# TFT_Display_Sheet.net
KiCad netlist of a schematic drawn in Altium Designer
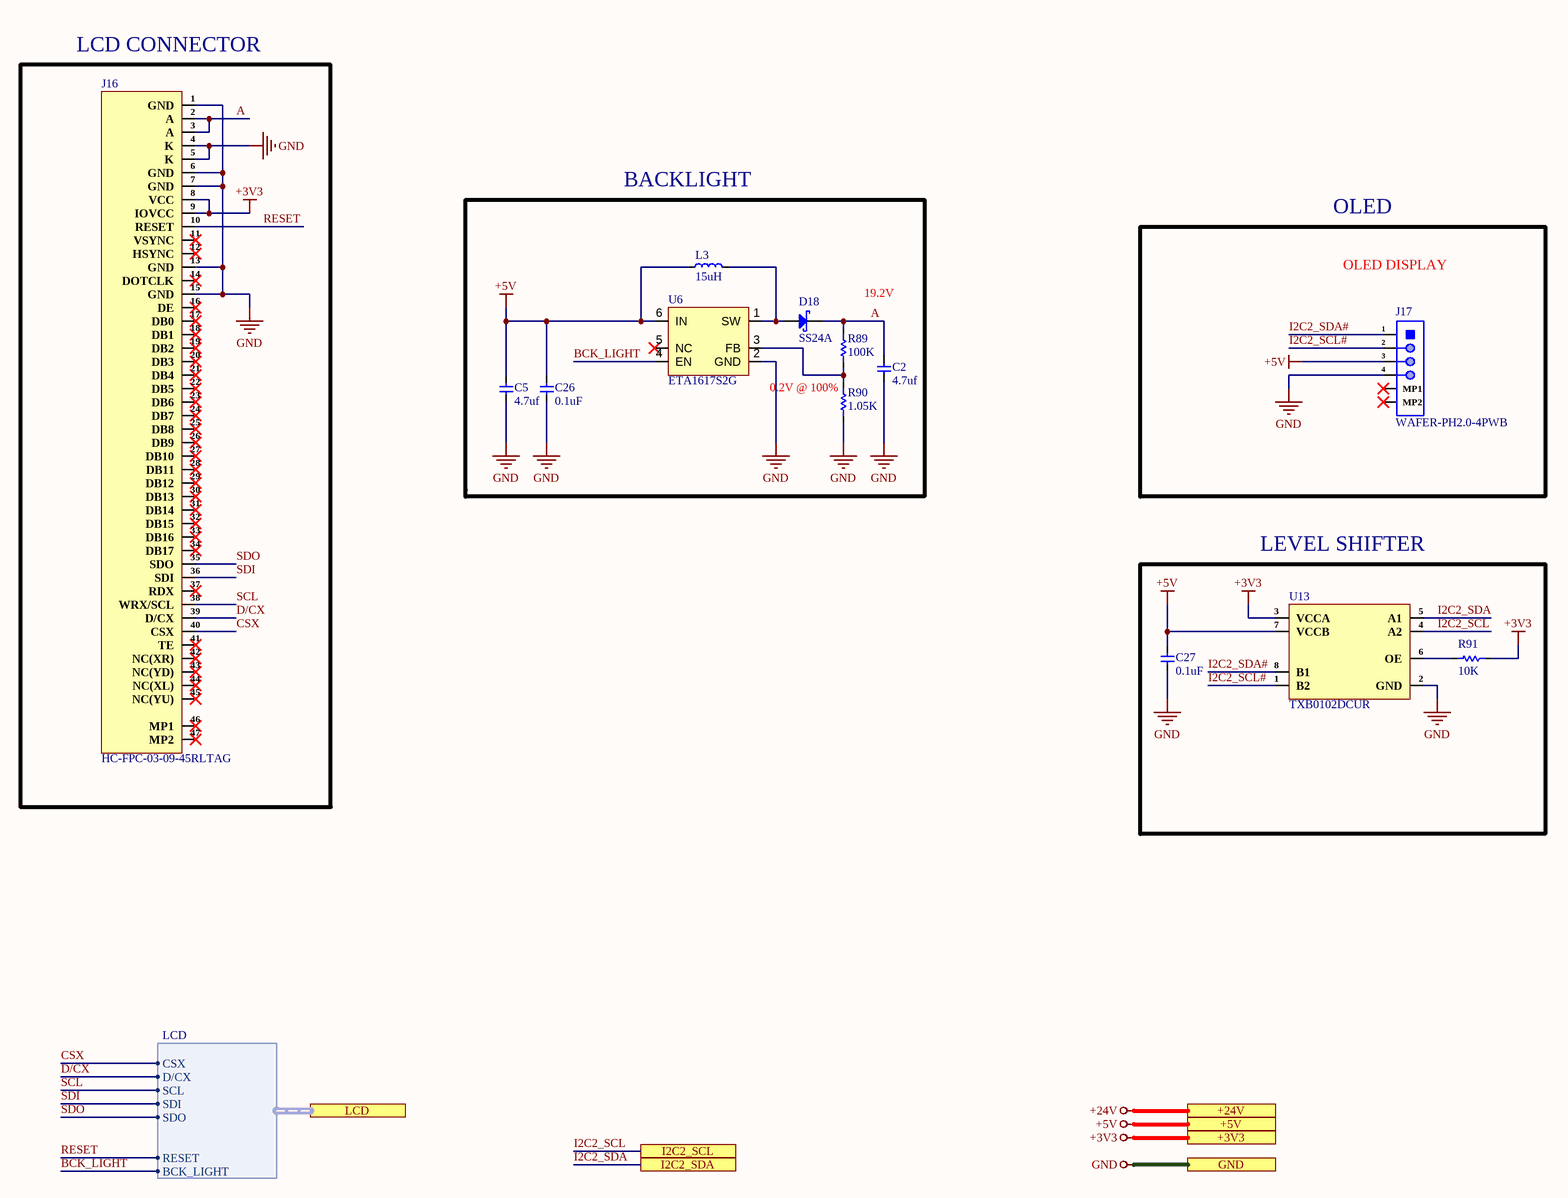
[diagram p0: TFT_Display_Sheet.SchDoc]

(export (version "E")
  (design (tool "Eeschema 10.0.6"))
  (components
    (comp (ref "C2")
      (value "4.7uf")
      (footprint "Cap-0805")
      (description "CAP CER 4.7UF 50V X5R 0805")
      (fields
        (field (name "MANUFACTURER") "Murata")
        (field (name "MANUFACTURER PART NUMBER") "GRM21BR61H475KE51L")
      )
      (libsource (lib "eSpark Libraries") (part "GRM21BR61H475KE51L"))
    )
    (comp (ref "C5")
      (value "4.7uf")
      (footprint "Cap-0805")
      (description "CAP CER 4.7UF 50V X5R 0805")
      (fields
        (field (name "MANUFACTURER") "Murata")
        (field (name "MANUFACTURER PART NUMBER") "GRM21BR61H475KE51L")
      )
      (libsource (lib "eSpark Libraries") (part "GRM21BR61H475KE51L"))
    )
    (comp (ref "C26")
      (value "0.1uF")
      (footprint "Cap-0402")
      (description "CAP CER 0.1UF 50V X5R 0402")
      (fields
        (field (name "MANUFACTURER") "TDK")
        (field (name "MANUFACTURER PART NUMBER") "C1005X5R1H104K050BB")
      )
      (libsource (lib "eSpark Libraries") (part "C1005X5R1H104K050BB"))
    )
    (comp (ref "C27")
      (value "0.1uF")
      (footprint "Cap-0402")
      (description "CAP CER 0.1UF 50V X5R 0402")
      (fields
        (field (name "MANUFACTURER") "TDK")
        (field (name "MANUFACTURER PART NUMBER") "C1005X5R1H104K050BB")
      )
      (libsource (lib "eSpark Libraries") (part "C1005X5R1H104K050BB"))
    )
    (comp (ref "D18")
      (value "SS24A")
      (footprint "SMA")
      (description "40V 500mV@2A 2A SMA(DO-214AC) Schottky Barrier Diodes (SBD) ROHS")
      (fields (field (name "MANUFACTURER") "Guangdong Hottech") (field (name "LCSC PART NUMBER") "C2886579"))
      (libsource (lib "eSpark Libraries") (part "SS24A"))
    )
    (comp (ref "J16")
      (value "HC-FPC-03-09-45RLTAG")
      (footprint "HC-FPC-03-09-45RLTAG")
      (fields (field (name "MANUFACTURER") "HCTL") (field (name "LCSC PART NUMBER") "C5213725"))
      (libsource (lib "eSpark Libraries") (part "HC-FPC-03-09-45RLTAG"))
    )
    (comp (ref "J17")
      (value "WAFER-PH2.0-4PWB")
      (footprint "WAFER-PH2.0-4PWB")
      (fields (field (name "LCSC PART NUMBER") "C3029442"))
      (libsource (lib "eSpark Libraries") (part "WAFER-PH2.0-4PWB"))
    )
    (comp (ref "L3")
      (value "15uH")
      (footprint "FXL0530-150-M")
      (description "1.7A 15uH Molding Choke ±20% 2.2A SMD,5.2x5.4mm Power Inductors ROHS")
      (fields
        (field (name "MANUFACTURER") "cjiang")
        (field (name "MANUFACTURER PART NUMBER") "FXL0530-150-M")
      )
      (libsource (lib "eSpark Libraries") (part "FXL0530-150-M"))
    )
    (comp (ref "R89")
      (value "100K")
      (footprint "Res-0402")
      (description "RES 100K OHM 1% 1/16W 0402")
      (fields
        (field (name "MANUFACTURER") "Yageo")
        (field (name "MANUFACTURER PART NUMBER") "RC0402FR-07100KL")
      )
      (libsource (lib "eSpark Libraries") (part "RC0402FR-07100KL"))
    )
    (comp (ref "R90")
      (value "1.05K")
      (footprint "Res-0402")
      (description "62.5mW Thick Film Resistors 50V ±100ppm/℃ ±1% 1.05kΩ 0402 Chip Resistor - Surface Mount ROHS")
      (fields
        (field (name "MANUFACTURER") "UNI-Royal")
        (field (name "MANUFACTURER PART NUMBER") "0402WGF1051TCE")
      )
      (libsource (lib "Schlib1") (part "0402WGF1051TCE"))
    )
    (comp (ref "R91")
      (value "10K")
      (footprint "Res-0402")
      (description "RES 10K OHM 1% 1/16W 0402")
      (fields
        (field (name "MANUFACTURER") "Yageo")
        (field (name "MANUFACTURER PART NUMBER") "RC0402FR-0710KL")
      )
      (libsource (lib "eSpark Libraries") (part "RC0402FR-0710KL"))
    )
    (comp (ref "U6")
      (value "ETA1617S2G")
      (footprint "SOT23-6")
      (description "SOT23-6 LED Drivers ROHS")
      (fields (field (name "MANUFACTURER") "etasolutions") (field (name "LCSC PART NUMBER") "C7465515"))
      (libsource (lib "Schlib1") (part "ETA1617S2G"))
    )
    (comp (ref "U13")
      (value "TXB0102DCUR")
      (footprint "VSSOP-8(3.1x2.1)")
      (description "IC TRANSLTR BIDIRECTIONAL 8VSSOP")
      (fields (field (name "MANUFACTURER") "Texas Instruments") (field (name "LCSC PART NUMBER") "C60709"))
      (libsource (lib "eSpark Libraries") (part "TXB0102DCUR"))
    )
  )
  (nets
    (net (code "2") (name "+3V3") (class "Default")
      (node (ref "J16") (pin "8") (pinfunction "VCC_8") (pintype "passive"))
      (node (ref "J16") (pin "9") (pinfunction "IOVCC_9") (pintype "passive"))
      (node (ref "R91") (pin "2") (pinfunction "2_2") (pintype "passive"))
      (node (ref "U13") (pin "3") (pinfunction "VCCA_3") (pintype "passive"))
    )
    (net (code "3") (name "+5V") (class "Default")
      (node (ref "C26") (pin "2") (pinfunction "2_2") (pintype "passive"))
      (node (ref "C27") (pin "2") (pinfunction "2_2") (pintype "passive"))
      (node (ref "C5") (pin "2") (pinfunction "2_2") (pintype "passive"))
      (node (ref "J17") (pin "3") (pinfunction "3_3") (pintype "passive"))
      (node (ref "L3") (pin "1") (pinfunction "1_1") (pintype "passive"))
      (node (ref "U13") (pin "7") (pinfunction "VCCB_7") (pintype "passive"))
      (node (ref "U6") (pin "6") (pinfunction "IN_6") (pintype "passive"))
    )
    (net (code "5") (name "/A") (class "Default")
      (node (ref "C2") (pin "2") (pinfunction "2_2") (pintype "passive"))
      (node (ref "D18") (pin "1") (pinfunction "K_1") (pintype "passive"))
      (node (ref "J16") (pin "2") (pinfunction "A_2") (pintype "passive"))
      (node (ref "J16") (pin "3") (pinfunction "A_3") (pintype "passive"))
      (node (ref "R89") (pin "2") (pinfunction "2_2") (pintype "passive"))
    )
    (net (code "6") (name "/BCK_LIGHT") (class "Default")
      (node (ref "U6") (pin "4") (pinfunction "EN_4") (pintype "passive"))
    )
    (net (code "7") (name "/CSX") (class "Default")
      (node (ref "J16") (pin "40") (pinfunction "CSX_40") (pintype "passive"))
    )
    (net (code "8") (name "/D{slash}CX") (class "Default")
      (node (ref "J16") (pin "39") (pinfunction "D/CX_39") (pintype "passive"))
    )
    (net (code "9") (name "/I2C2_SCL") (class "Default")
      (node (ref "U13") (pin "4") (pinfunction "A2_4") (pintype "passive"))
    )
    (net (code "10") (name "/I2C2_SCL#") (class "Default")
      (node (ref "J17") (pin "2") (pinfunction "2_2") (pintype "passive"))
      (node (ref "U13") (pin "1") (pinfunction "B2_1") (pintype "passive"))
    )
    (net (code "11") (name "/I2C2_SDA") (class "Default")
      (node (ref "U13") (pin "5") (pinfunction "A1_5") (pintype "passive"))
    )
    (net (code "12") (name "/I2C2_SDA#") (class "Default")
      (node (ref "J17") (pin "1") (pinfunction "1_1") (pintype "passive"))
      (node (ref "U13") (pin "8") (pinfunction "B1_8") (pintype "passive"))
    )
    (net (code "13") (name "/RESET") (class "Default")
      (node (ref "J16") (pin "10") (pinfunction "RESET_10") (pintype "passive"))
    )
    (net (code "14") (name "/SCL") (class "Default")
      (node (ref "J16") (pin "38") (pinfunction "WRX/SCL_38") (pintype "passive"))
    )
    (net (code "15") (name "/SDI") (class "Default")
      (node (ref "J16") (pin "36") (pinfunction "SDI_36") (pintype "passive"))
    )
    (net (code "16") (name "/SDO") (class "Default")
      (node (ref "J16") (pin "35") (pinfunction "SDO_35") (pintype "passive"))
    )
    (net (code "18") (name "GND") (class "Default")
      (node (ref "C2") (pin "1") (pinfunction "1_1") (pintype "passive"))
      (node (ref "C26") (pin "1") (pinfunction "1_1") (pintype "passive"))
      (node (ref "C27") (pin "1") (pinfunction "1_1") (pintype "passive"))
      (node (ref "C5") (pin "1") (pinfunction "1_1") (pintype "passive"))
      (node (ref "J16") (pin "1") (pinfunction "GND_1") (pintype "passive"))
      (node (ref "J16") (pin "13") (pinfunction "GND_13") (pintype "passive"))
      (node (ref "J16") (pin "15") (pinfunction "GND_15") (pintype "passive"))
      (node (ref "J16") (pin "4") (pinfunction "K_4") (pintype "passive"))
      (node (ref "J16") (pin "5") (pinfunction "K_5") (pintype "passive"))
      (node (ref "J16") (pin "6") (pinfunction "GND_6") (pintype "passive"))
      (node (ref "J16") (pin "7") (pinfunction "GND_7") (pintype "passive"))
      (node (ref "J17") (pin "4") (pinfunction "4_4") (pintype "passive"))
      (node (ref "R90") (pin "1") (pinfunction "1_1") (pintype "passive"))
      (node (ref "U13") (pin "2") (pinfunction "GND_2") (pintype "passive"))
      (node (ref "U6") (pin "2") (pinfunction "GND_2") (pintype "passive"))
    )
    (net (code "19") (name "Net-(D18-A)") (class "Default")
      (node (ref "D18") (pin "2") (pinfunction "A_2") (pintype "passive"))
      (node (ref "L3") (pin "2") (pinfunction "2_2") (pintype "passive"))
      (node (ref "U6") (pin "1") (pinfunction "SW_1") (pintype "passive"))
    )
    (net (code "20") (name "Net-(U6-FB)") (class "Default")
      (node (ref "R89") (pin "1") (pinfunction "1_1") (pintype "passive"))
      (node (ref "R90") (pin "2") (pinfunction "2_2") (pintype "passive"))
      (node (ref "U6") (pin "3") (pinfunction "FB_3") (pintype "passive"))
    )
    (net (code "21") (name "Net-(U13-OE)") (class "Default")
      (node (ref "R91") (pin "1") (pinfunction "1_1") (pintype "passive"))
      (node (ref "U13") (pin "6") (pinfunction "OE_6") (pintype "passive"))
    )
    (net (code "22") (name "unconnected-(J16-DB0-Pad17)") (class "Default")
      (node (ref "J16") (pin "17") (pinfunction "DB0_17") (pintype "passive+no_connect"))
    )
    (net (code "23") (name "unconnected-(J16-DB1-Pad18)") (class "Default")
      (node (ref "J16") (pin "18") (pinfunction "DB1_18") (pintype "passive+no_connect"))
    )
    (net (code "24") (name "unconnected-(J16-DB2-Pad19)") (class "Default")
      (node (ref "J16") (pin "19") (pinfunction "DB2_19") (pintype "passive+no_connect"))
    )
    (net (code "25") (name "unconnected-(J16-DB3-Pad20)") (class "Default")
      (node (ref "J16") (pin "20") (pinfunction "DB3_20") (pintype "passive+no_connect"))
    )
    (net (code "26") (name "unconnected-(J16-DB4-Pad21)") (class "Default")
      (node (ref "J16") (pin "21") (pinfunction "DB4_21") (pintype "passive+no_connect"))
    )
    (net (code "27") (name "unconnected-(J16-DB5-Pad22)") (class "Default")
      (node (ref "J16") (pin "22") (pinfunction "DB5_22") (pintype "passive+no_connect"))
    )
    (net (code "28") (name "unconnected-(J16-DB6-Pad23)") (class "Default")
      (node (ref "J16") (pin "23") (pinfunction "DB6_23") (pintype "passive+no_connect"))
    )
    (net (code "29") (name "unconnected-(J16-DB7-Pad24)") (class "Default")
      (node (ref "J16") (pin "24") (pinfunction "DB7_24") (pintype "passive+no_connect"))
    )
    (net (code "30") (name "unconnected-(J16-DB8-Pad25)") (class "Default")
      (node (ref "J16") (pin "25") (pinfunction "DB8_25") (pintype "passive+no_connect"))
    )
    (net (code "31") (name "unconnected-(J16-DB9-Pad26)") (class "Default")
      (node (ref "J16") (pin "26") (pinfunction "DB9_26") (pintype "passive+no_connect"))
    )
    (net (code "32") (name "unconnected-(J16-DB10-Pad27)") (class "Default")
      (node (ref "J16") (pin "27") (pinfunction "DB10_27") (pintype "passive+no_connect"))
    )
    (net (code "33") (name "unconnected-(J16-DB11-Pad28)") (class "Default")
      (node (ref "J16") (pin "28") (pinfunction "DB11_28") (pintype "passive+no_connect"))
    )
    (net (code "34") (name "unconnected-(J16-DB12-Pad29)") (class "Default")
      (node (ref "J16") (pin "29") (pinfunction "DB12_29") (pintype "passive+no_connect"))
    )
    (net (code "35") (name "unconnected-(J16-DB13-Pad30)") (class "Default")
      (node (ref "J16") (pin "30") (pinfunction "DB13_30") (pintype "passive+no_connect"))
    )
    (net (code "36") (name "unconnected-(J16-DB14-Pad31)") (class "Default")
      (node (ref "J16") (pin "31") (pinfunction "DB14_31") (pintype "passive+no_connect"))
    )
    (net (code "37") (name "unconnected-(J16-DB15-Pad32)") (class "Default")
      (node (ref "J16") (pin "32") (pinfunction "DB15_32") (pintype "passive+no_connect"))
    )
    (net (code "38") (name "unconnected-(J16-DB16-Pad33)") (class "Default")
      (node (ref "J16") (pin "33") (pinfunction "DB16_33") (pintype "passive+no_connect"))
    )
    (net (code "39") (name "unconnected-(J16-DB17-Pad34)") (class "Default")
      (node (ref "J16") (pin "34") (pinfunction "DB17_34") (pintype "passive+no_connect"))
    )
    (net (code "40") (name "unconnected-(J16-DE-Pad16)") (class "Default")
      (node (ref "J16") (pin "16") (pinfunction "DE_16") (pintype "passive+no_connect"))
    )
    (net (code "41") (name "unconnected-(J16-DOTCLK-Pad14)") (class "Default")
      (node (ref "J16") (pin "14") (pinfunction "DOTCLK_14") (pintype "passive+no_connect"))
    )
    (net (code "42") (name "unconnected-(J16-HSYNC-Pad12)") (class "Default")
      (node (ref "J16") (pin "12") (pinfunction "HSYNC_12") (pintype "passive+no_connect"))
    )
    (net (code "43") (name "unconnected-(J16-MP1-Pad46)") (class "Default")
      (node (ref "J16") (pin "46") (pinfunction "MP1_46") (pintype "passive+no_connect"))
    )
    (net (code "44") (name "unconnected-(J16-MP2-Pad47)") (class "Default")
      (node (ref "J16") (pin "47") (pinfunction "MP2_47") (pintype "passive+no_connect"))
    )
    (net (code "45") (name "unconnected-(J16-NC(XL)-Pad44)") (class "Default")
      (node (ref "J16") (pin "44") (pinfunction "NC(XL)_44") (pintype "passive+no_connect"))
    )
    (net (code "46") (name "unconnected-(J16-NC(XR)-Pad42)") (class "Default")
      (node (ref "J16") (pin "42") (pinfunction "NC(XR)_42") (pintype "passive+no_connect"))
    )
    (net (code "47") (name "unconnected-(J16-NC(YD)-Pad43)") (class "Default")
      (node (ref "J16") (pin "43") (pinfunction "NC(YD)_43") (pintype "passive+no_connect"))
    )
    (net (code "48") (name "unconnected-(J16-NC(YU)-Pad45)") (class "Default")
      (node (ref "J16") (pin "45") (pinfunction "NC(YU)_45") (pintype "passive+no_connect"))
    )
    (net (code "49") (name "unconnected-(J16-RDX-Pad37)") (class "Default")
      (node (ref "J16") (pin "37") (pinfunction "RDX_37") (pintype "passive+no_connect"))
    )
    (net (code "50") (name "unconnected-(J16-TE-Pad41)") (class "Default")
      (node (ref "J16") (pin "41") (pinfunction "TE_41") (pintype "passive+no_connect"))
    )
    (net (code "51") (name "unconnected-(J16-VSYNC-Pad11)") (class "Default")
      (node (ref "J16") (pin "11") (pinfunction "VSYNC_11") (pintype "passive+no_connect"))
    )
    (net (code "52") (name "unconnected-(J17-PadMP1)") (class "Default")
      (node (ref "J17") (pin "MP1") (pinfunction "MP1_MP1") (pintype "passive+no_connect"))
    )
    (net (code "53") (name "unconnected-(J17-PadMP2)") (class "Default")
      (node (ref "J17") (pin "MP2") (pinfunction "MP2_MP2") (pintype "passive+no_connect"))
    )
    (net (code "54") (name "unconnected-(U6-NC-Pad5)") (class "Default")
      (node (ref "U6") (pin "5") (pinfunction "NC_5") (pintype "passive+no_connect"))
    )
  )
)
